# 05_MCU-Part2.net
KiCad netlist of a schematic drawn in Altium Designer
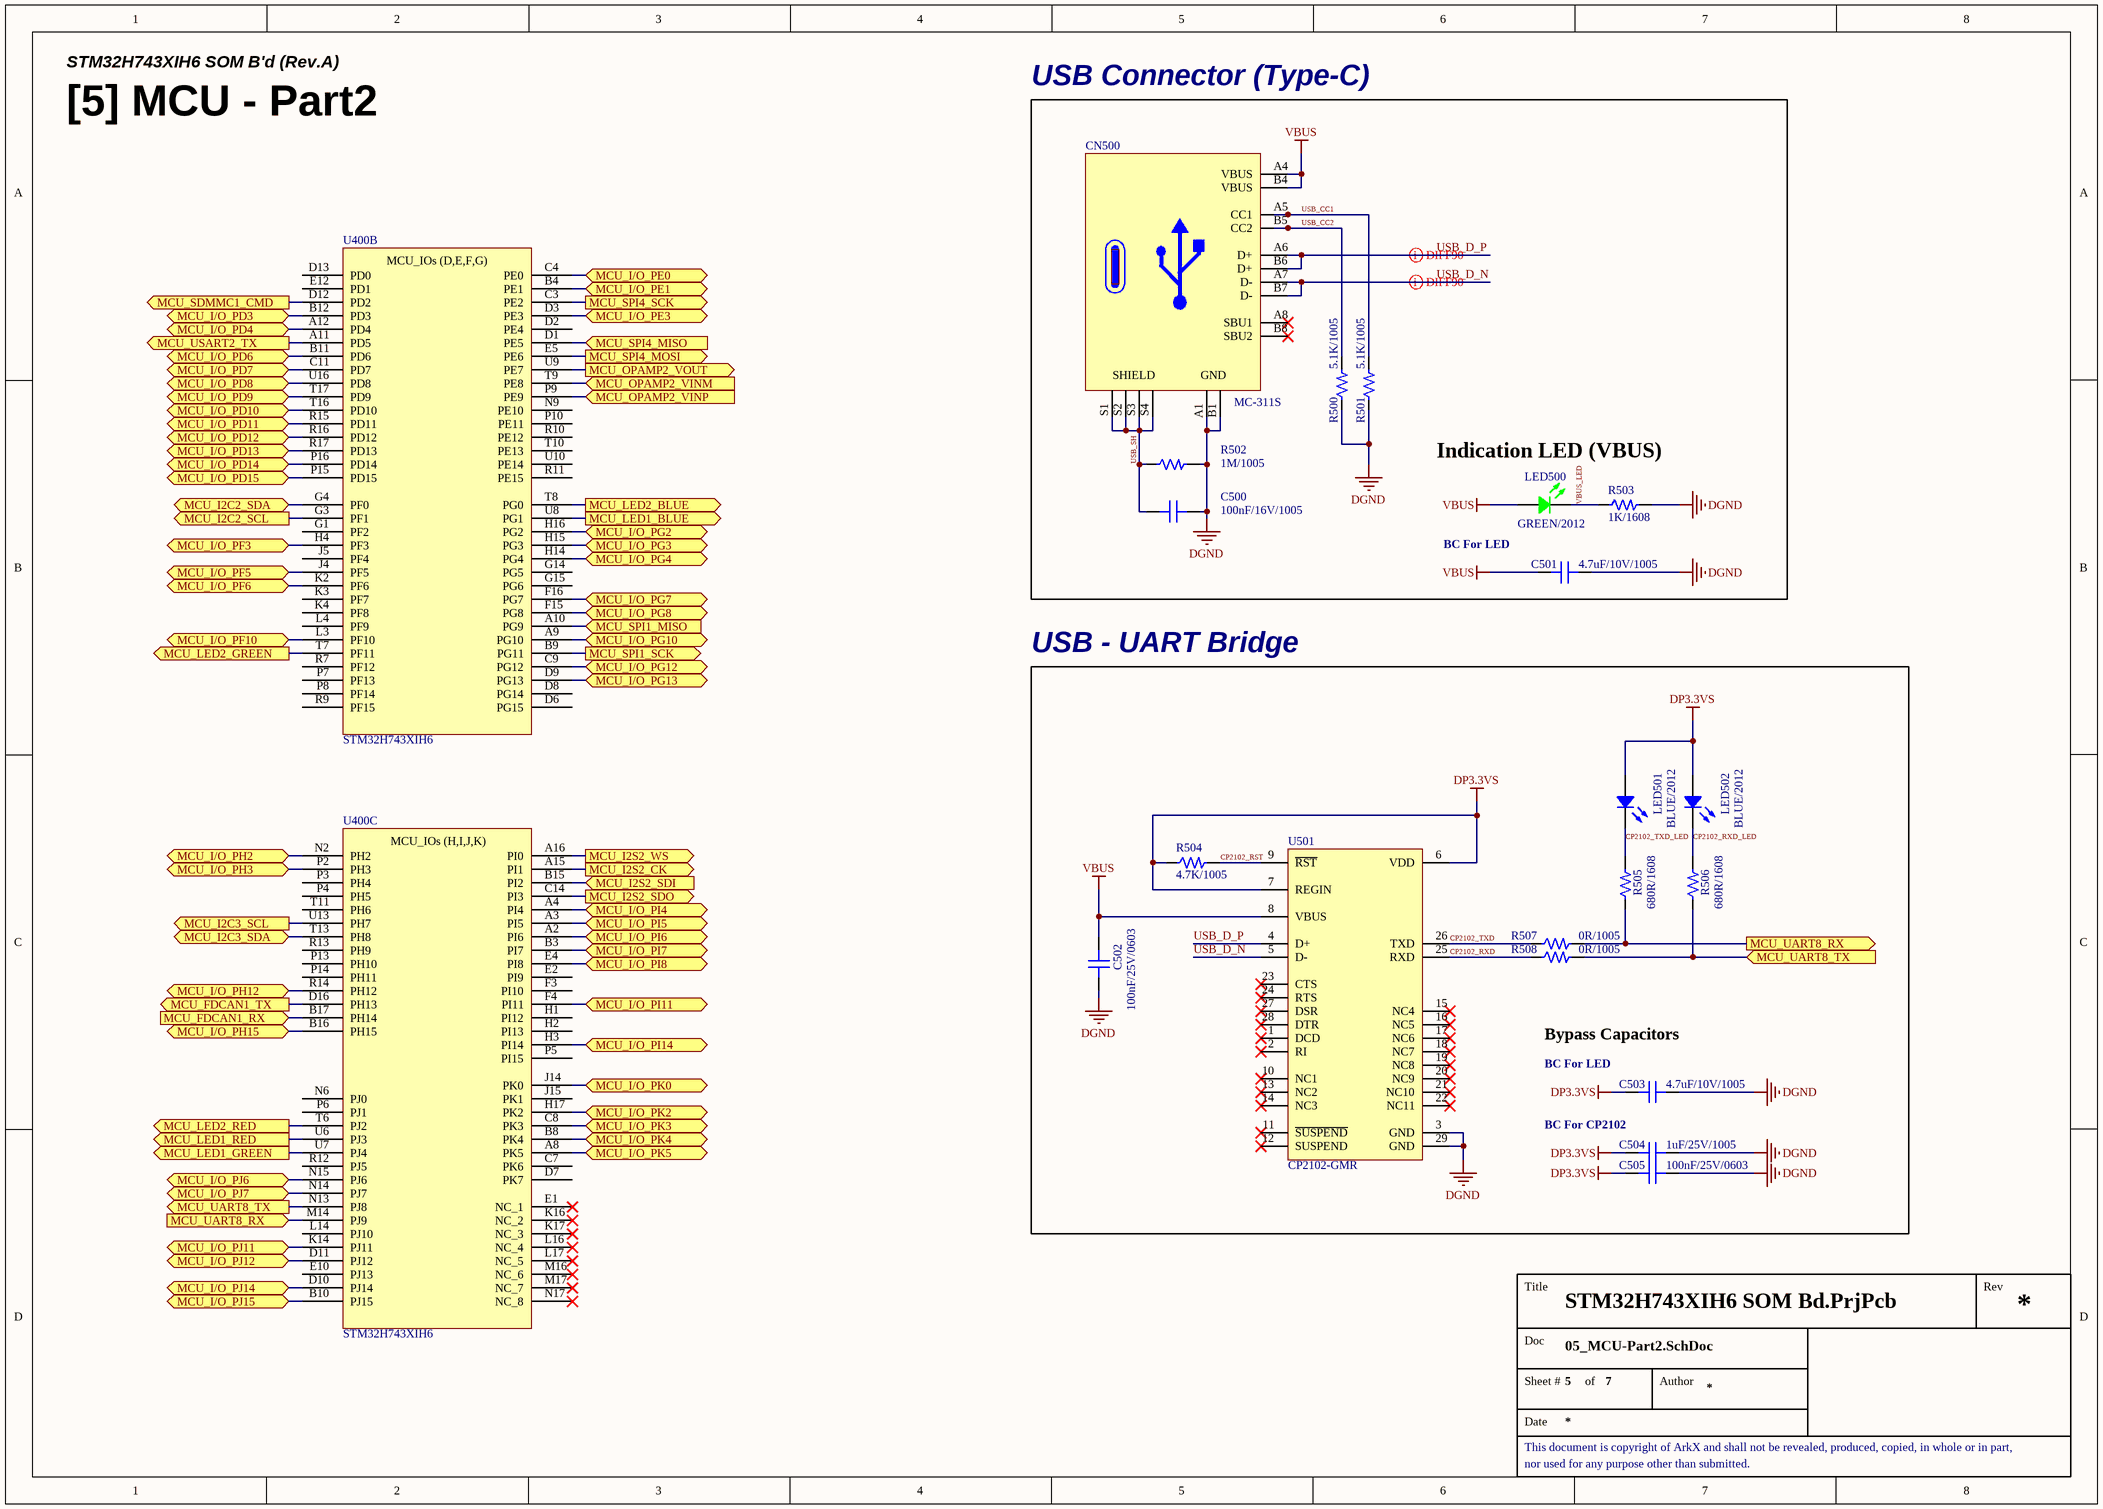
[diagram p0: 05_MCU-Part2.SchDoc]

(export (version "E")
  (design (tool "Eeschema 10.0.6"))
  (components
    (comp (ref "C500")
      (value "100nF/16V/1005")
      (footprint "CAP 1005 (0402_INCH)")
      (description "Ceramic CAP_100nF/16V/1005")
      (fields (field (name "LCSC PART #") "C1525"))
      (libsource (lib "Arkx") (part "CAP_100nF/16V/1005"))
    )
    (comp (ref "C501")
      (value "4.7uF/10V/1005")
      (footprint "CAP 1005 (0402_INCH)")
      (description "10V 4.7uF X5R ±20% 0402  Multilayer Ceramic Capacitors MLCC - SMD/SMT ROHS")
      (fields (field (name "LCSC PART #") "C23733"))
      (libsource (lib "Arkx") (part "CAP_4.7uF/10V/1005"))
    )
    (comp (ref "C502")
      (value "100nF/25V/0603")
      (footprint "CAP 0603 (0201_INCH)")
      (description "Ceramic CAP_100nF/25V/0603")
      (fields (field (name "LCSC PART #") "C181047"))
      (libsource (lib "Arkx") (part "CAP_100nF/25V/0603"))
    )
    (comp (ref "C503")
      (value "4.7uF/10V/1005")
      (footprint "CAP 1005 (0402_INCH)")
      (description "10V 4.7uF X5R ±20% 0402  Multilayer Ceramic Capacitors MLCC - SMD/SMT ROHS")
      (fields (field (name "LCSC PART #") "C23733"))
      (libsource (lib "Arkx") (part "CAP_4.7uF/10V/1005"))
    )
    (comp (ref "C504")
      (value "1uF/25V/1005")
      (footprint "CAP 1005 (0402_INCH)")
      (description "Ceramic CAP_1uF/25V/1005")
      (fields (field (name "LCSC PART #") "C52923"))
      (libsource (lib "Arkx") (part "CAP_1uF/25V/1005"))
    )
    (comp (ref "C505")
      (value "100nF/25V/0603")
      (footprint "CAP 0603 (0201_INCH)")
      (description "Ceramic CAP_100nF/25V/0603")
      (fields (field (name "LCSC PART #") "C181047"))
      (libsource (lib "Arkx") (part "CAP_100nF/25V/0603"))
    )
    (comp (ref "CN500")
      (value "MC-311S")
      (footprint "CON USB-Type-C (16P)")
      (description "USB 2.0 5A 1 Surface Mount 16 Female -35℃~+75℃ Type-C SMD  USB Connectors ROHS")
      (fields (field (name "LCSC PART #") "C2977718"))
      (libsource (lib "Arkx") (part "CON_USB-Type-C"))
    )
    (comp (ref "LED500")
      (value "GREEN/2012")
      (footprint "LED MHT170RGBCT (GREEN)")
      (fields (field (name "LCSC PART #") "C2962094"))
      (libsource (lib "Arkx") (part "LED_MHT170RGBCT(GREEN)"))
    )
    (comp (ref "LED501")
      (value "BLUE/2012")
      (footprint "LED MHT170RGBCT (BLUE)")
      (fields (field (name "LCSC PART #") "C2962094"))
      (libsource (lib "Arkx") (part "LED_MHT170RGBCT(BLUE)"))
    )
    (comp (ref "LED502")
      (value "BLUE/2012")
      (footprint "LED MHT170RGBCT (BLUE)")
      (fields (field (name "LCSC PART #") "C2962094"))
      (libsource (lib "Arkx") (part "LED_MHT170RGBCT(BLUE)"))
    )
    (comp (ref "R500")
      (value "5.1K/1005")
      (footprint "RES 1005 (0402_inch)")
      (description "RES_5.1K/1005/62.5mW")
      (fields (field (name "LCSC PART #") "C25905"))
      (libsource (lib "Arkx") (part "RES_5.1K/1005/62.5mW"))
    )
    (comp (ref "R501")
      (value "5.1K/1005")
      (footprint "RES 1005 (0402_inch)")
      (description "RES_5.1K/1005/62.5mW")
      (fields (field (name "LCSC PART #") "C25905"))
      (libsource (lib "Arkx") (part "RES_5.1K/1005/62.5mW"))
    )
    (comp (ref "R502")
      (value "1M/1005")
      (footprint "RES 1005 (0402_inch)")
      (description "RES_1M/1005/62.5mW")
      (fields (field (name "LCSC PART #") "C26083"))
      (libsource (lib "Arkx") (part "RES_1M/1005/62.5mW"))
    )
    (comp (ref "R503")
      (value "1K/1608")
      (footprint "RES 1608 (0603_inch)")
      (description "RES_1K/1608/0.1W")
      (fields (field (name "LCSC PART #") "C21190"))
      (libsource (lib "Arkx") (part "RES_1K/1608/0.1W"))
    )
    (comp (ref "R504")
      (value "4.7K/1005")
      (footprint "RES 1005 (0402_inch)")
      (description "RES_4.7K/1005/62.5mW")
      (fields (field (name "LCSC PART #") "C25900"))
      (libsource (lib "Arkx") (part "RES_4.7K/1005/62.5mW"))
    )
    (comp (ref "R505")
      (value "680R/1608")
      (footprint "RES 1608 (0603_inch)")
      (description "RES_680R/1608/0.1W")
      (fields (field (name "LCSC PART #") "C23228"))
      (libsource (lib "Arkx") (part "RES_680R/1608/0.1W"))
    )
    (comp (ref "R506")
      (value "680R/1608")
      (footprint "RES 1608 (0603_inch)")
      (description "RES_680R/1608/0.1W")
      (fields (field (name "LCSC PART #") "C23228"))
      (libsource (lib "Arkx") (part "RES_680R/1608/0.1W"))
    )
    (comp (ref "R507")
      (value "0R/1005")
      (footprint "RES 1005 (0402_inch)")
      (description "RES_0R/1005/62.5mW")
      (fields (field (name "LCSC PART #") "C17168"))
      (libsource (lib "Arkx") (part "RES_0R/1005/62.5mW"))
    )
    (comp (ref "R508")
      (value "0R/1005")
      (footprint "RES 1005 (0402_inch)")
      (description "RES_0R/1005/62.5mW")
      (fields (field (name "LCSC PART #") "C17168"))
      (libsource (lib "Arkx") (part "RES_0R/1005/62.5mW"))
    )
    (comp (ref "U400")
      (value "STM32H743XIH6")
      (footprint "IC TFBGA-265")
      (description "ARM® Cortex®-M7 STM32H7 MCU IC 32bit Single-core 480MHz 2MB(2M x 8) Flash 240+25-TFBGA(14x14)")
      (fields (field (name "LCSC PART #") "C114407"))
      (libsource (lib "Arkx") (part "IC_MCU_STM32H743XIH6"))
    )
    (comp (ref "U501")
      (value "CP2102-GMR")
      (footprint "QFN-28 (5x5mm)")
      (description "Transceiver 1Mbps USB 1/1 QFN-28_5x5x05P  USB ICs ROHS")
      (fields (field (name "LCSC PART #") "C6568"))
      (libsource (lib "Arkx") (part "IC_USB_CP2102"))
    )
  )
  (nets
    (net (code "1") (name "/CP2102_RST") (class "Default")
      (node (ref "R504") (pin "2") (pinfunction "2_2") (pintype "passive"))
      (node (ref "U501") (pin "9") (pinfunction "~{RST}_9") (pintype "passive"))
    )
    (net (code "2") (name "/CP2102_RXD") (class "Default")
      (node (ref "R508") (pin "1") (pinfunction "1_1") (pintype "passive"))
      (node (ref "U501") (pin "25") (pinfunction "RXD_25") (pintype "passive"))
    )
    (net (code "3") (name "/CP2102_RXD_LED") (class "Default")
      (node (ref "LED502") (pin "3") (pinfunction "BLUE_3") (pintype "passive"))
      (node (ref "R506") (pin "2") (pinfunction "2_2") (pintype "passive"))
    )
    (net (code "4") (name "/CP2102_TXD") (class "Default")
      (node (ref "R507") (pin "1") (pinfunction "1_1") (pintype "passive"))
      (node (ref "U501") (pin "26") (pinfunction "TXD_26") (pintype "passive"))
    )
    (net (code "5") (name "/CP2102_TXD_LED") (class "Default")
      (node (ref "LED501") (pin "3") (pinfunction "BLUE_3") (pintype "passive"))
      (node (ref "R505") (pin "2") (pinfunction "2_2") (pintype "passive"))
    )
    (net (code "6") (name "/MCU_FDCAN1_RX") (class "Default")
      (node (ref "U400") (pin "B17") (pinfunction "PH14_B17") (pintype "passive"))
    )
    (net (code "7") (name "/MCU_FDCAN1_TX") (class "Default")
      (node (ref "U400") (pin "D16") (pinfunction "PH13_D16") (pintype "passive"))
    )
    (net (code "8") (name "/MCU_I2C2_SCL") (class "Default")
      (node (ref "U400") (pin "G3") (pinfunction "PF1_G3") (pintype "passive"))
    )
    (net (code "9") (name "/MCU_I2C2_SDA") (class "Default")
      (node (ref "U400") (pin "G4") (pinfunction "PF0_G4") (pintype "passive"))
    )
    (net (code "10") (name "/MCU_I2C3_SCL") (class "Default")
      (node (ref "U400") (pin "U13") (pinfunction "PH7_U13") (pintype "passive"))
    )
    (net (code "11") (name "/MCU_I2C3_SDA") (class "Default")
      (node (ref "U400") (pin "T13") (pinfunction "PH8_T13") (pintype "passive"))
    )
    (net (code "12") (name "/MCU_I2S2_CK") (class "Default")
      (node (ref "U400") (pin "A15") (pinfunction "PI1_A15") (pintype "passive"))
    )
    (net (code "13") (name "/MCU_I2S2_SDI") (class "Default")
      (node (ref "U400") (pin "B15") (pinfunction "PI2_B15") (pintype "passive"))
    )
    (net (code "14") (name "/MCU_I2S2_SDO") (class "Default")
      (node (ref "U400") (pin "C14") (pinfunction "PI3_C14") (pintype "passive"))
    )
    (net (code "15") (name "/MCU_I2S2_WS") (class "Default")
      (node (ref "U400") (pin "A16") (pinfunction "PI0_A16") (pintype "passive"))
    )
    (net (code "16") (name "/MCU_I{slash}O_PD3") (class "Default")
      (node (ref "U400") (pin "B12") (pinfunction "PD3_B12") (pintype "passive"))
    )
    (net (code "17") (name "/MCU_I{slash}O_PD4") (class "Default")
      (node (ref "U400") (pin "A12") (pinfunction "PD4_A12") (pintype "passive"))
    )
    (net (code "18") (name "/MCU_I{slash}O_PD6") (class "Default")
      (node (ref "U400") (pin "B11") (pinfunction "PD6_B11") (pintype "passive"))
    )
    (net (code "19") (name "/MCU_I{slash}O_PD7") (class "Default")
      (node (ref "U400") (pin "C11") (pinfunction "PD7_C11") (pintype "passive"))
    )
    (net (code "20") (name "/MCU_I{slash}O_PD8") (class "Default")
      (node (ref "U400") (pin "U16") (pinfunction "PD8_U16") (pintype "passive"))
    )
    (net (code "21") (name "/MCU_I{slash}O_PD9") (class "Default")
      (node (ref "U400") (pin "T17") (pinfunction "PD9_T17") (pintype "passive"))
    )
    (net (code "22") (name "/MCU_I{slash}O_PD10") (class "Default")
      (node (ref "U400") (pin "T16") (pinfunction "PD10_T16") (pintype "passive"))
    )
    (net (code "23") (name "/MCU_I{slash}O_PD11") (class "Default")
      (node (ref "U400") (pin "R15") (pinfunction "PD11_R15") (pintype "passive"))
    )
    (net (code "24") (name "/MCU_I{slash}O_PD12") (class "Default")
      (node (ref "U400") (pin "R16") (pinfunction "PD12_R16") (pintype "passive"))
    )
    (net (code "25") (name "/MCU_I{slash}O_PD13") (class "Default")
      (node (ref "U400") (pin "R17") (pinfunction "PD13_R17") (pintype "passive"))
    )
    (net (code "26") (name "/MCU_I{slash}O_PD14") (class "Default")
      (node (ref "U400") (pin "P16") (pinfunction "PD14_P16") (pintype "passive"))
    )
    (net (code "27") (name "/MCU_I{slash}O_PD15") (class "Default")
      (node (ref "U400") (pin "P15") (pinfunction "PD15_P15") (pintype "passive"))
    )
    (net (code "28") (name "/MCU_I{slash}O_PE0") (class "Default")
      (node (ref "U400") (pin "C4") (pinfunction "PE0_C4") (pintype "passive"))
    )
    (net (code "29") (name "/MCU_I{slash}O_PE1") (class "Default")
      (node (ref "U400") (pin "B4") (pinfunction "PE1_B4") (pintype "passive"))
    )
    (net (code "30") (name "/MCU_I{slash}O_PE3") (class "Default")
      (node (ref "U400") (pin "D3") (pinfunction "PE3_D3") (pintype "passive"))
    )
    (net (code "31") (name "/MCU_I{slash}O_PF3") (class "Default")
      (node (ref "U400") (pin "H4") (pinfunction "PF3_H4") (pintype "passive"))
    )
    (net (code "32") (name "/MCU_I{slash}O_PF5") (class "Default")
      (node (ref "U400") (pin "J4") (pinfunction "PF5_J4") (pintype "passive"))
    )
    (net (code "33") (name "/MCU_I{slash}O_PF6") (class "Default")
      (node (ref "U400") (pin "K2") (pinfunction "PF6_K2") (pintype "passive"))
    )
    (net (code "34") (name "/MCU_I{slash}O_PF10") (class "Default")
      (node (ref "U400") (pin "L3") (pinfunction "PF10_L3") (pintype "passive"))
    )
    (net (code "35") (name "/MCU_I{slash}O_PG2") (class "Default")
      (node (ref "U400") (pin "H16") (pinfunction "PG2_H16") (pintype "passive"))
    )
    (net (code "36") (name "/MCU_I{slash}O_PG3") (class "Default")
      (node (ref "U400") (pin "H15") (pinfunction "PG3_H15") (pintype "passive"))
    )
    (net (code "37") (name "/MCU_I{slash}O_PG4") (class "Default")
      (node (ref "U400") (pin "H14") (pinfunction "PG4_H14") (pintype "passive"))
    )
    (net (code "38") (name "/MCU_I{slash}O_PG7") (class "Default")
      (node (ref "U400") (pin "F16") (pinfunction "PG7_F16") (pintype "passive"))
    )
    (net (code "39") (name "/MCU_I{slash}O_PG8") (class "Default")
      (node (ref "U400") (pin "F15") (pinfunction "PG8_F15") (pintype "passive"))
    )
    (net (code "40") (name "/MCU_I{slash}O_PG10") (class "Default")
      (node (ref "U400") (pin "A9") (pinfunction "PG10_A9") (pintype "passive"))
    )
    (net (code "41") (name "/MCU_I{slash}O_PG12") (class "Default")
      (node (ref "U400") (pin "C9") (pinfunction "PG12_C9") (pintype "passive"))
    )
    (net (code "42") (name "/MCU_I{slash}O_PG13") (class "Default")
      (node (ref "U400") (pin "D9") (pinfunction "PG13_D9") (pintype "passive"))
    )
    (net (code "43") (name "/MCU_I{slash}O_PH2") (class "Default")
      (node (ref "U400") (pin "N2") (pinfunction "PH2_N2") (pintype "passive"))
    )
    (net (code "44") (name "/MCU_I{slash}O_PH3") (class "Default")
      (node (ref "U400") (pin "P2") (pinfunction "PH3_P2") (pintype "passive"))
    )
    (net (code "45") (name "/MCU_I{slash}O_PH12") (class "Default")
      (node (ref "U400") (pin "R14") (pinfunction "PH12_R14") (pintype "passive"))
    )
    (net (code "46") (name "/MCU_I{slash}O_PH15") (class "Default")
      (node (ref "U400") (pin "B16") (pinfunction "PH15_B16") (pintype "passive"))
    )
    (net (code "47") (name "/MCU_I{slash}O_PI4") (class "Default")
      (node (ref "U400") (pin "A4") (pinfunction "PI4_A4") (pintype "passive"))
    )
    (net (code "48") (name "/MCU_I{slash}O_PI5") (class "Default")
      (node (ref "U400") (pin "A3") (pinfunction "PI5_A3") (pintype "passive"))
    )
    (net (code "49") (name "/MCU_I{slash}O_PI6") (class "Default")
      (node (ref "U400") (pin "A2") (pinfunction "PI6_A2") (pintype "passive"))
    )
    (net (code "50") (name "/MCU_I{slash}O_PI7") (class "Default")
      (node (ref "U400") (pin "B3") (pinfunction "PI7_B3") (pintype "passive"))
    )
    (net (code "51") (name "/MCU_I{slash}O_PI8") (class "Default")
      (node (ref "U400") (pin "E4") (pinfunction "PI8_E4") (pintype "passive"))
    )
    (net (code "52") (name "/MCU_I{slash}O_PI11") (class "Default")
      (node (ref "U400") (pin "F4") (pinfunction "PI11_F4") (pintype "passive"))
    )
    (net (code "53") (name "/MCU_I{slash}O_PI14") (class "Default")
      (node (ref "U400") (pin "H3") (pinfunction "PI14_H3") (pintype "passive"))
    )
    (net (code "54") (name "/MCU_I{slash}O_PJ6") (class "Default")
      (node (ref "U400") (pin "N15") (pinfunction "PJ6_N15") (pintype "passive"))
    )
    (net (code "55") (name "/MCU_I{slash}O_PJ7") (class "Default")
      (node (ref "U400") (pin "N14") (pinfunction "PJ7_N14") (pintype "passive"))
    )
    (net (code "56") (name "/MCU_I{slash}O_PJ11") (class "Default")
      (node (ref "U400") (pin "K14") (pinfunction "PJ11_K14") (pintype "passive"))
    )
    (net (code "57") (name "/MCU_I{slash}O_PJ12") (class "Default")
      (node (ref "U400") (pin "D11") (pinfunction "PJ12_D11") (pintype "passive"))
    )
    (net (code "58") (name "/MCU_I{slash}O_PJ14") (class "Default")
      (node (ref "U400") (pin "D10") (pinfunction "PJ14_D10") (pintype "passive"))
    )
    (net (code "59") (name "/MCU_I{slash}O_PJ15") (class "Default")
      (node (ref "U400") (pin "B10") (pinfunction "PJ15_B10") (pintype "passive"))
    )
    (net (code "60") (name "/MCU_I{slash}O_PK0") (class "Default")
      (node (ref "U400") (pin "J14") (pinfunction "PK0_J14") (pintype "passive"))
    )
    (net (code "61") (name "/MCU_I{slash}O_PK2") (class "Default")
      (node (ref "U400") (pin "H17") (pinfunction "PK2_H17") (pintype "passive"))
    )
    (net (code "62") (name "/MCU_I{slash}O_PK3") (class "Default")
      (node (ref "U400") (pin "C8") (pinfunction "PK3_C8") (pintype "passive"))
    )
    (net (code "63") (name "/MCU_I{slash}O_PK4") (class "Default")
      (node (ref "U400") (pin "B8") (pinfunction "PK4_B8") (pintype "passive"))
    )
    (net (code "64") (name "/MCU_I{slash}O_PK5") (class "Default")
      (node (ref "U400") (pin "A8") (pinfunction "PK5_A8") (pintype "passive"))
    )
    (net (code "65") (name "/MCU_LED1_BLUE") (class "Default")
      (node (ref "U400") (pin "U8") (pinfunction "PG1_U8") (pintype "passive"))
    )
    (net (code "66") (name "/MCU_LED1_GREEN") (class "Default")
      (node (ref "U400") (pin "U7") (pinfunction "PJ4_U7") (pintype "passive"))
    )
    (net (code "67") (name "/MCU_LED1_RED") (class "Default")
      (node (ref "U400") (pin "U6") (pinfunction "PJ3_U6") (pintype "passive"))
    )
    (net (code "68") (name "/MCU_LED2_BLUE") (class "Default")
      (node (ref "U400") (pin "T8") (pinfunction "PG0_T8") (pintype "passive"))
    )
    (net (code "69") (name "/MCU_LED2_GREEN") (class "Default")
      (node (ref "U400") (pin "T7") (pinfunction "PF11_T7") (pintype "passive"))
    )
    (net (code "70") (name "/MCU_LED2_RED") (class "Default")
      (node (ref "U400") (pin "T6") (pinfunction "PJ2_T6") (pintype "passive"))
    )
    (net (code "71") (name "/MCU_OPAMP2_VINM") (class "Default")
      (node (ref "U400") (pin "T9") (pinfunction "PE8_T9") (pintype "passive"))
    )
    (net (code "72") (name "/MCU_OPAMP2_VINP") (class "Default")
      (node (ref "U400") (pin "P9") (pinfunction "PE9_P9") (pintype "passive"))
    )
    (net (code "73") (name "/MCU_OPAMP2_VOUT") (class "Default")
      (node (ref "U400") (pin "U9") (pinfunction "PE7_U9") (pintype "passive"))
    )
    (net (code "74") (name "/MCU_SDMMC1_CMD") (class "Default")
      (node (ref "U400") (pin "D12") (pinfunction "PD2_D12") (pintype "passive"))
    )
    (net (code "75") (name "/MCU_SPI1_MISO") (class "Default")
      (node (ref "U400") (pin "A10") (pinfunction "PG9_A10") (pintype "passive"))
    )
    (net (code "76") (name "/MCU_SPI1_SCK") (class "Default")
      (node (ref "U400") (pin "B9") (pinfunction "PG11_B9") (pintype "passive"))
    )
    (net (code "77") (name "/MCU_SPI4_MISO") (class "Default")
      (node (ref "U400") (pin "D1") (pinfunction "PE5_D1") (pintype "passive"))
    )
    (net (code "78") (name "/MCU_SPI4_MOSI") (class "Default")
      (node (ref "U400") (pin "E5") (pinfunction "PE6_E5") (pintype "passive"))
    )
    (net (code "79") (name "/MCU_SPI4_SCK") (class "Default")
      (node (ref "U400") (pin "C3") (pinfunction "PE2_C3") (pintype "passive"))
    )
    (net (code "80") (name "/MCU_UART8_RX") (class "Default")
      (node (ref "R505") (pin "1") (pinfunction "1_1") (pintype "passive"))
      (node (ref "R507") (pin "2") (pinfunction "2_2") (pintype "passive"))
      (node (ref "U400") (pin "M14") (pinfunction "PJ9_M14") (pintype "passive"))
    )
    (net (code "81") (name "/MCU_UART8_TX") (class "Default")
      (node (ref "R506") (pin "1") (pinfunction "1_1") (pintype "passive"))
      (node (ref "R508") (pin "2") (pinfunction "2_2") (pintype "passive"))
      (node (ref "U400") (pin "N13") (pinfunction "PJ8_N13") (pintype "passive"))
    )
    (net (code "82") (name "/MCU_USART2_TX") (class "Default")
      (node (ref "U400") (pin "A11") (pinfunction "PD5_A11") (pintype "passive"))
    )
    (net (code "83") (name "/USB_CC1") (class "Default")
      (node (ref "CN500") (pin "A5") (pinfunction "CC1_A5") (pintype "passive"))
      (node (ref "R501") (pin "2") (pinfunction "2_2") (pintype "passive"))
    )
    (net (code "84") (name "/USB_CC2") (class "Default")
      (node (ref "CN500") (pin "B5") (pinfunction "CC2_B5") (pintype "passive"))
      (node (ref "R500") (pin "2") (pinfunction "2_2") (pintype "passive"))
    )
    (net (code "85") (name "/USB_D_N") (class "Default")
      (node (ref "CN500") (pin "A7") (pinfunction "D-_A7") (pintype "passive"))
      (node (ref "CN500") (pin "B7") (pinfunction "D-_B7") (pintype "passive"))
      (node (ref "U501") (pin "5") (pinfunction "D-_5") (pintype "passive"))
    )
    (net (code "86") (name "/USB_D_P") (class "Default")
      (node (ref "CN500") (pin "A6") (pinfunction "D+_A6") (pintype "passive"))
      (node (ref "CN500") (pin "B6") (pinfunction "D+_B6") (pintype "passive"))
      (node (ref "U501") (pin "4") (pinfunction "D+_4") (pintype "passive"))
    )
    (net (code "87") (name "/USB_SH") (class "Default")
      (node (ref "C500") (pin "2") (pinfunction "2_2") (pintype "passive"))
      (node (ref "CN500") (pin "S1") (pinfunction "SHIELD_S1") (pintype "passive"))
      (node (ref "CN500") (pin "S2") (pinfunction "SHIELD_S2") (pintype "passive"))
      (node (ref "CN500") (pin "S3") (pinfunction "SHIELD_S3") (pintype "passive"))
      (node (ref "CN500") (pin "S4") (pinfunction "SHIELD_S4") (pintype "passive"))
      (node (ref "R502") (pin "1") (pinfunction "1_1") (pintype "passive"))
    )
    (net (code "88") (name "/VBUS_LED") (class "Default")
      (node (ref "LED500") (pin "2") (pinfunction "GREEN_2") (pintype "passive"))
      (node (ref "R503") (pin "1") (pinfunction "1_1") (pintype "passive"))
    )
    (net (code "89") (name "DGND") (class "Default")
      (node (ref "C500") (pin "1") (pinfunction "1_1") (pintype "passive"))
      (node (ref "C501") (pin "1") (pinfunction "1_1") (pintype "passive"))
      (node (ref "C502") (pin "2") (pinfunction "2_2") (pintype "passive"))
      (node (ref "C503") (pin "1") (pinfunction "1_1") (pintype "passive"))
      (node (ref "C504") (pin "2") (pinfunction "2_2") (pintype "passive"))
      (node (ref "C505") (pin "1") (pinfunction "1_1") (pintype "passive"))
      (node (ref "CN500") (pin "A1") (pinfunction "GND_A1") (pintype "passive"))
      (node (ref "CN500") (pin "B1") (pinfunction "GND_B1") (pintype "passive"))
      (node (ref "R500") (pin "1") (pinfunction "1_1") (pintype "passive"))
      (node (ref "R501") (pin "1") (pinfunction "1_1") (pintype "passive"))
      (node (ref "R502") (pin "2") (pinfunction "2_2") (pintype "passive"))
      (node (ref "R503") (pin "2") (pinfunction "2_2") (pintype "passive"))
      (node (ref "U501") (pin "29") (pinfunction "GND_29") (pintype "passive"))
      (node (ref "U501") (pin "3") (pinfunction "GND_3") (pintype "passive"))
    )
    (net (code "90") (name "DP3.3VS") (class "Default")
      (node (ref "C503") (pin "2") (pinfunction "2_2") (pintype "passive"))
      (node (ref "C504") (pin "1") (pinfunction "1_1") (pintype "passive"))
      (node (ref "C505") (pin "2") (pinfunction "2_2") (pintype "passive"))
      (node (ref "LED501") (pin "4") (pinfunction "Common_Anode_4") (pintype "passive"))
      (node (ref "LED502") (pin "4") (pinfunction "Common_Anode_4") (pintype "passive"))
      (node (ref "R504") (pin "1") (pinfunction "1_1") (pintype "passive"))
      (node (ref "U501") (pin "6") (pinfunction "VDD_6") (pintype "passive"))
      (node (ref "U501") (pin "7") (pinfunction "REGIN_7") (pintype "passive"))
    )
    (net (code "91") (name "VBUS") (class "Default")
      (node (ref "C501") (pin "2") (pinfunction "2_2") (pintype "passive"))
      (node (ref "C502") (pin "1") (pinfunction "1_1") (pintype "passive"))
      (node (ref "CN500") (pin "A4") (pinfunction "VBUS_A4") (pintype "passive"))
      (node (ref "CN500") (pin "B4") (pinfunction "VBUS_B4") (pintype "passive"))
      (node (ref "LED500") (pin "4") (pinfunction "Common_Anode_4") (pintype "passive"))
      (node (ref "U501") (pin "8") (pinfunction "VBUS_8") (pintype "passive"))
    )
    (net (code "92") (name "unconnected-(CN500-SBU1-PadA8)") (class "Default")
      (node (ref "CN500") (pin "A8") (pinfunction "SBU1_A8") (pintype "passive+no_connect"))
    )
    (net (code "93") (name "unconnected-(CN500-SBU2-PadB8)") (class "Default")
      (node (ref "CN500") (pin "B8") (pinfunction "SBU2_B8") (pintype "passive+no_connect"))
    )
    (net (code "94") (name "unconnected-(U400B-PD0-PadD13)") (class "Default")
      (node (ref "U400") (pin "D13") (pinfunction "PD0_D13") (pintype "passive"))
    )
    (net (code "95") (name "unconnected-(U400B-PD1-PadE12)") (class "Default")
      (node (ref "U400") (pin "E12") (pinfunction "PD1_E12") (pintype "passive"))
    )
    (net (code "96") (name "unconnected-(U400B-PE4-PadD2)") (class "Default")
      (node (ref "U400") (pin "D2") (pinfunction "PE4_D2") (pintype "passive"))
    )
    (net (code "97") (name "unconnected-(U400B-PE10-PadN9)") (class "Default")
      (node (ref "U400") (pin "N9") (pinfunction "PE10_N9") (pintype "passive"))
    )
    (net (code "98") (name "unconnected-(U400B-PE11-PadP10)") (class "Default")
      (node (ref "U400") (pin "P10") (pinfunction "PE11_P10") (pintype "passive"))
    )
    (net (code "99") (name "unconnected-(U400B-PE12-PadR10)") (class "Default")
      (node (ref "U400") (pin "R10") (pinfunction "PE12_R10") (pintype "passive"))
    )
    (net (code "100") (name "unconnected-(U400B-PE13-PadT10)") (class "Default")
      (node (ref "U400") (pin "T10") (pinfunction "PE13_T10") (pintype "passive"))
    )
    (net (code "101") (name "unconnected-(U400B-PE14-PadU10)") (class "Default")
      (node (ref "U400") (pin "U10") (pinfunction "PE14_U10") (pintype "passive"))
    )
    (net (code "102") (name "unconnected-(U400B-PE15-PadR11)") (class "Default")
      (node (ref "U400") (pin "R11") (pinfunction "PE15_R11") (pintype "passive"))
    )
    (net (code "103") (name "unconnected-(U400B-PF2-PadG1)") (class "Default")
      (node (ref "U400") (pin "G1") (pinfunction "PF2_G1") (pintype "passive"))
    )
    (net (code "104") (name "unconnected-(U400B-PF4-PadJ5)") (class "Default")
      (node (ref "U400") (pin "J5") (pinfunction "PF4_J5") (pintype "passive"))
    )
    (net (code "105") (name "unconnected-(U400B-PF7-PadK3)") (class "Default")
      (node (ref "U400") (pin "K3") (pinfunction "PF7_K3") (pintype "passive"))
    )
    (net (code "106") (name "unconnected-(U400B-PF8-PadK4)") (class "Default")
      (node (ref "U400") (pin "K4") (pinfunction "PF8_K4") (pintype "passive"))
    )
    (net (code "107") (name "unconnected-(U400B-PF9-PadL4)") (class "Default")
      (node (ref "U400") (pin "L4") (pinfunction "PF9_L4") (pintype "passive"))
    )
    (net (code "108") (name "unconnected-(U400B-PF12-PadR7)") (class "Default")
      (node (ref "U400") (pin "R7") (pinfunction "PF12_R7") (pintype "passive"))
    )
    (net (code "109") (name "unconnected-(U400B-PF13-PadP7)") (class "Default")
      (node (ref "U400") (pin "P7") (pinfunction "PF13_P7") (pintype "passive"))
    )
    (net (code "110") (name "unconnected-(U400B-PF14-PadP8)") (class "Default")
      (node (ref "U400") (pin "P8") (pinfunction "PF14_P8") (pintype "passive"))
    )
    (net (code "111") (name "unconnected-(U400B-PF15-PadR9)") (class "Default")
      (node (ref "U400") (pin "R9") (pinfunction "PF15_R9") (pintype "passive"))
    )
    (net (code "112") (name "unconnected-(U400B-PG5-PadG14)") (class "Default")
      (node (ref "U400") (pin "G14") (pinfunction "PG5_G14") (pintype "passive"))
    )
    (net (code "113") (name "unconnected-(U400B-PG6-PadG15)") (class "Default")
      (node (ref "U400") (pin "G15") (pinfunction "PG6_G15") (pintype "passive"))
    )
    (net (code "114") (name "unconnected-(U400B-PG14-PadD8)") (class "Default")
      (node (ref "U400") (pin "D8") (pinfunction "PG14_D8") (pintype "passive"))
    )
    (net (code "115") (name "unconnected-(U400B-PG15-PadD6)") (class "Default")
      (node (ref "U400") (pin "D6") (pinfunction "PG15_D6") (pintype "passive"))
    )
    (net (code "116") (name "unconnected-(U400C-NC_1-PadE1)") (class "Default")
      (node (ref "U400") (pin "E1") (pinfunction "NC_1_E1") (pintype "passive+no_connect"))
    )
    (net (code "117") (name "unconnected-(U400C-NC_2-PadK16)") (class "Default")
      (node (ref "U400") (pin "K16") (pinfunction "NC_2_K16") (pintype "passive+no_connect"))
    )
    (net (code "118") (name "unconnected-(U400C-NC_3-PadK17)") (class "Default")
      (node (ref "U400") (pin "K17") (pinfunction "NC_3_K17") (pintype "passive+no_connect"))
    )
    (net (code "119") (name "unconnected-(U400C-NC_4-PadL16)") (class "Default")
      (node (ref "U400") (pin "L16") (pinfunction "NC_4_L16") (pintype "passive+no_connect"))
    )
    (net (code "120") (name "unconnected-(U400C-NC_5-PadL17)") (class "Default")
      (node (ref "U400") (pin "L17") (pinfunction "NC_5_L17") (pintype "passive+no_connect"))
    )
    (net (code "121") (name "unconnected-(U400C-NC_6-PadM16)") (class "Default")
      (node (ref "U400") (pin "M16") (pinfunction "NC_6_M16") (pintype "passive+no_connect"))
    )
    (net (code "122") (name "unconnected-(U400C-NC_7-PadM17)") (class "Default")
      (node (ref "U400") (pin "M17") (pinfunction "NC_7_M17") (pintype "passive+no_connect"))
    )
    (net (code "123") (name "unconnected-(U400C-NC_8-PadN17)") (class "Default")
      (node (ref "U400") (pin "N17") (pinfunction "NC_8_N17") (pintype "passive+no_connect"))
    )
    (net (code "124") (name "unconnected-(U400C-PH4-PadP3)") (class "Default")
      (node (ref "U400") (pin "P3") (pinfunction "PH4_P3") (pintype "passive"))
    )
    (net (code "125") (name "unconnected-(U400C-PH5-PadP4)") (class "Default")
      (node (ref "U400") (pin "P4") (pinfunction "PH5_P4") (pintype "passive"))
    )
    (net (code "126") (name "unconnected-(U400C-PH6-PadT11)") (class "Default")
      (node (ref "U400") (pin "T11") (pinfunction "PH6_T11") (pintype "passive"))
    )
    (net (code "127") (name "unconnected-(U400C-PH9-PadR13)") (class "Default")
      (node (ref "U400") (pin "R13") (pinfunction "PH9_R13") (pintype "passive"))
    )
    (net (code "128") (name "unconnected-(U400C-PH10-PadP13)") (class "Default")
      (node (ref "U400") (pin "P13") (pinfunction "PH10_P13") (pintype "passive"))
    )
    (net (code "129") (name "unconnected-(U400C-PH11-PadP14)") (class "Default")
      (node (ref "U400") (pin "P14") (pinfunction "PH11_P14") (pintype "passive"))
    )
    (net (code "130") (name "unconnected-(U400C-PI9-PadE2)") (class "Default")
      (node (ref "U400") (pin "E2") (pinfunction "PI9_E2") (pintype "passive"))
    )
    (net (code "131") (name "unconnected-(U400C-PI10-PadF3)") (class "Default")
      (node (ref "U400") (pin "F3") (pinfunction "PI10_F3") (pintype "passive"))
    )
    (net (code "132") (name "unconnected-(U400C-PI12-PadH1)") (class "Default")
      (node (ref "U400") (pin "H1") (pinfunction "PI12_H1") (pintype "passive"))
    )
    (net (code "133") (name "unconnected-(U400C-PI13-PadH2)") (class "Default")
      (node (ref "U400") (pin "H2") (pinfunction "PI13_H2") (pintype "passive"))
    )
    (net (code "134") (name "unconnected-(U400C-PI15-PadP5)") (class "Default")
      (node (ref "U400") (pin "P5") (pinfunction "PI15_P5") (pintype "passive"))
    )
    (net (code "135") (name "unconnected-(U400C-PJ0-PadN6)") (class "Default")
      (node (ref "U400") (pin "N6") (pinfunction "PJ0_N6") (pintype "passive"))
    )
    (net (code "136") (name "unconnected-(U400C-PJ1-PadP6)") (class "Default")
      (node (ref "U400") (pin "P6") (pinfunction "PJ1_P6") (pintype "passive"))
    )
    (net (code "137") (name "unconnected-(U400C-PJ5-PadR12)") (class "Default")
      (node (ref "U400") (pin "R12") (pinfunction "PJ5_R12") (pintype "passive"))
    )
    (net (code "138") (name "unconnected-(U400C-PJ10-PadL14)") (class "Default")
      (node (ref "U400") (pin "L14") (pinfunction "PJ10_L14") (pintype "passive"))
    )
    (net (code "139") (name "unconnected-(U400C-PJ13-PadE10)") (class "Default")
      (node (ref "U400") (pin "E10") (pinfunction "PJ13_E10") (pintype "passive"))
    )
    (net (code "140") (name "unconnected-(U400C-PK1-PadJ15)") (class "Default")
      (node (ref "U400") (pin "J15") (pinfunction "PK1_J15") (pintype "passive"))
    )
    (net (code "141") (name "unconnected-(U400C-PK6-PadC7)") (class "Default")
      (node (ref "U400") (pin "C7") (pinfunction "PK6_C7") (pintype "passive"))
    )
    (net (code "142") (name "unconnected-(U400C-PK7-PadD7)") (class "Default")
      (node (ref "U400") (pin "D7") (pinfunction "PK7_D7") (pintype "passive"))
    )
    (net (code "143") (name "unconnected-(U501-CTS-Pad23)") (class "Default")
      (node (ref "U501") (pin "23") (pinfunction "CTS_23") (pintype "passive+no_connect"))
    )
    (net (code "144") (name "unconnected-(U501-DCD-Pad1)") (class "Default")
      (node (ref "U501") (pin "1") (pinfunction "DCD_1") (pintype "passive+no_connect"))
    )
    (net (code "145") (name "unconnected-(U501-DSR-Pad27)") (class "Default")
      (node (ref "U501") (pin "27") (pinfunction "DSR_27") (pintype "passive+no_connect"))
    )
    (net (code "146") (name "unconnected-(U501-DTR-Pad28)") (class "Default")
      (node (ref "U501") (pin "28") (pinfunction "DTR_28") (pintype "passive+no_connect"))
    )
    (net (code "147") (name "unconnected-(U501-NC1-Pad10)") (class "Default")
      (node (ref "U501") (pin "10") (pinfunction "NC1_10") (pintype "passive+no_connect"))
    )
    (net (code "148") (name "unconnected-(U501-NC2-Pad13)") (class "Default")
      (node (ref "U501") (pin "13") (pinfunction "NC2_13") (pintype "passive+no_connect"))
    )
    (net (code "149") (name "unconnected-(U501-NC3-Pad14)") (class "Default")
      (node (ref "U501") (pin "14") (pinfunction "NC3_14") (pintype "passive+no_connect"))
    )
    (net (code "150") (name "unconnected-(U501-NC4-Pad15)") (class "Default")
      (node (ref "U501") (pin "15") (pinfunction "NC4_15") (pintype "passive+no_connect"))
    )
    (net (code "151") (name "unconnected-(U501-NC5-Pad16)") (class "Default")
      (node (ref "U501") (pin "16") (pinfunction "NC5_16") (pintype "passive+no_connect"))
    )
    (net (code "152") (name "unconnected-(U501-NC6-Pad17)") (class "Default")
      (node (ref "U501") (pin "17") (pinfunction "NC6_17") (pintype "passive+no_connect"))
    )
    (net (code "153") (name "unconnected-(U501-NC7-Pad18)") (class "Default")
      (node (ref "U501") (pin "18") (pinfunction "NC7_18") (pintype "passive+no_connect"))
    )
    (net (code "154") (name "unconnected-(U501-NC8-Pad19)") (class "Default")
      (node (ref "U501") (pin "19") (pinfunction "NC8_19") (pintype "passive+no_connect"))
    )
    (net (code "155") (name "unconnected-(U501-NC9-Pad20)") (class "Default")
      (node (ref "U501") (pin "20") (pinfunction "NC9_20") (pintype "passive+no_connect"))
    )
    (net (code "156") (name "unconnected-(U501-NC10-Pad21)") (class "Default")
      (node (ref "U501") (pin "21") (pinfunction "NC10_21") (pintype "passive+no_connect"))
    )
    (net (code "157") (name "unconnected-(U501-NC11-Pad22)") (class "Default")
      (node (ref "U501") (pin "22") (pinfunction "NC11_22") (pintype "passive+no_connect"))
    )
    (net (code "158") (name "unconnected-(U501-RI-Pad2)") (class "Default")
      (node (ref "U501") (pin "2") (pinfunction "RI_2") (pintype "passive+no_connect"))
    )
    (net (code "159") (name "unconnected-(U501-RTS-Pad24)") (class "Default")
      (node (ref "U501") (pin "24") (pinfunction "RTS_24") (pintype "passive+no_connect"))
    )
    (net (code "160") (name "unconnected-(U501-SUSPEND-Pad12)") (class "Default")
      (node (ref "U501") (pin "12") (pinfunction "SUSPEND_12") (pintype "passive+no_connect"))
    )
    (net (code "161") (name "unconnected-(U501-~{SUSPEND}-Pad11)") (class "Default")
      (node (ref "U501") (pin "11") (pinfunction "~{SUSPEND}_11") (pintype "passive+no_connect"))
    )
  )
)
